# 10_SES.net
KiCad netlist of a schematic drawn in Altium Designer
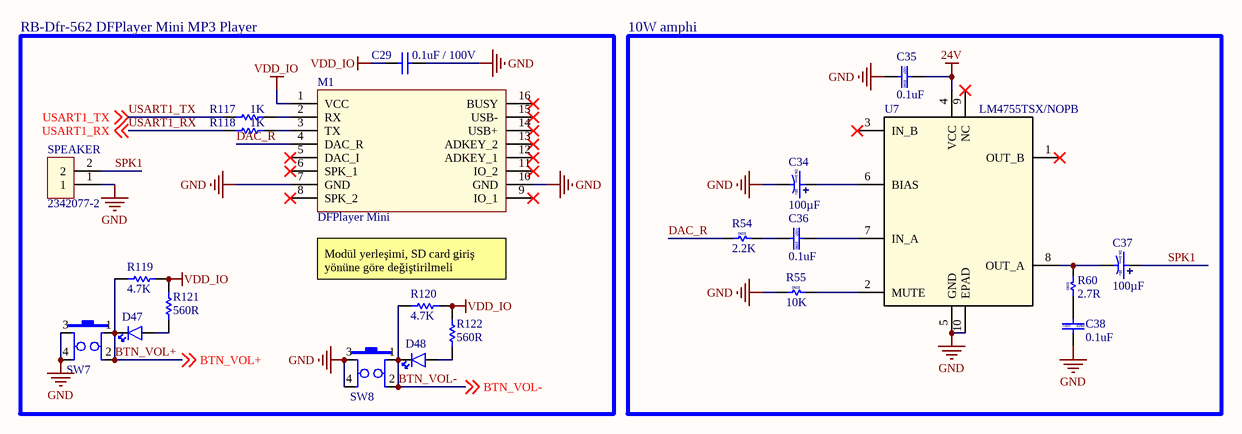
[diagram p0: 10_SES.SchDoc]

(export (version "E")
  (design (tool "Eeschema 10.0.6"))
  (components
    (comp (ref "C29")
      (value "0.1uF / 100V")
      (footprint "603C")
      (description "0.1 µF ±10% 100V Ceramic Capacitor X7R 0603 (1608 Metric)")
      (fields
        (field (name "DIGI-KEY PART NUMBER") "2679-C0603X7R101-104KNPTR-ND")
        (field (name "MANUFACTURER") "Venkel")
      )
      (libsource (lib "FKDZ_Altium_Lib") (part "CAP CER 0.1UF 100V X7R 0603"))
    )
    (comp (ref "C34")
      (value "100µF")
      (footprint "CAPALP_6.6x6.6mm")
      (description "100µF 35V Aluminum Electrolytic Capacitors Radial, Can - SMD 1000 Hrs @ 105°C")
      (fields (field (name "DIGI-KEY PART NUMBER") "493-2203-2-ND") (field (name "TOLERANCE") "±20%"))
      (libsource (lib "FKDZ_Altium_Lib") (part "CAP_ALP_100uF_35V_%20_DIA6.3mm"))
    )
    (comp (ref "C35")
      (value "0.1uF")
      (footprint "603C")
      (description "0.1 µF ±10% 100V Ceramic Capacitor X7R 0603 (1608 Metric)")
      (fields
        (field (name "DIGI-KEY PART NUMBER") "2679-C0603X7R101-104KNPTR-ND")
        (field (name "MANUFACTURER") "Venkel")
      )
      (libsource (lib "FKDZ_Altium_Lib") (part "CAP CER 0.1UF 100V X7R 0603"))
    )
    (comp (ref "C36")
      (value "0.1uF")
      (footprint "603C")
      (description "0.1 µF ±10% 100V Ceramic Capacitor X7R 0603 (1608 Metric)")
      (fields
        (field (name "DIGI-KEY PART NUMBER") "2679-C0603X7R101-104KNPTR-ND")
        (field (name "MANUFACTURER") "Venkel")
      )
      (libsource (lib "FKDZ_Altium_Lib") (part "CAP CER 0.1UF 100V X7R 0603"))
    )
    (comp (ref "C37")
      (value "100µF")
      (footprint "CAPALP_6.6x6.6mm")
      (description "100µF 35V Aluminum Electrolytic Capacitors Radial, Can - SMD 1000 Hrs @ 105°C")
      (fields (field (name "DIGI-KEY PART NUMBER") "493-2203-2-ND") (field (name "TOLERANCE") "±20%"))
      (libsource (lib "FKDZ_Altium_Lib") (part "CAP_ALP_100uF_35V_%20_DIA6.3mm"))
    )
    (comp (ref "C38")
      (value "0.1uF")
      (footprint "603C")
      (description "0.1 µF ±10% 100V Ceramic Capacitor X7R 0603 (1608 Metric)")
      (fields
        (field (name "DIGI-KEY PART NUMBER") "2679-C0603X7R101-104KNPTR-ND")
        (field (name "MANUFACTURER") "Venkel")
      )
      (libsource (lib "FKDZ_Altium_Lib") (part "CAP CER 0.1UF 100V X7R 0603"))
    )
    (comp (ref "D47")
      (value "led_green")
      (footprint "805LED")
      (description "LED 2X1.2MM 570NM GN WTR CLR SMD")
      (fields (field (name "DIGI-KEY PART NUMBER") "754-1127-1-ND"))
      (libsource (lib "FKDZ_Altium_Lib") (part "LED_GREEN_0805"))
    )
    (comp (ref "D48")
      (value "led_green")
      (footprint "805LED")
      (description "LED 2X1.2MM 570NM GN WTR CLR SMD")
      (fields (field (name "DIGI-KEY PART NUMBER") "754-1127-1-ND"))
      (libsource (lib "FKDZ_Altium_Lib") (part "LED_GREEN_0805"))
    )
    (comp (ref "M1")
      (value "DFPlayer Mini")
      (footprint "DFPLAYER MINI")
      (libsource (lib "FKDZ_Altium_Lib") (part "MP3 PLAYER MODULE DFPlayer Mini"))
    )
    (comp (ref "R54")
      (value "2.2K")
      (footprint "603R")
      (description "2.2 kOhms ±5% 0.1W, 1/10W Chip Resistor 0603 (1608 Metric) Automotive AEC-Q200 Thick Film")
      (fields (field (name "DIGI-KEY PART NUMBER") "RMCF0603JT2K20TR-ND") (field (name "TOLERANCE") "±5%"))
      (libsource (lib "FKDZ_Altium_Lib") (part "RES 2.2K OHM 5% 1/10W 0603"))
    )
    (comp (ref "R55")
      (value "10K")
      (footprint "603R")
      (description "10 kOhms ±5% 0.1W, 1/10W Chip Resistor 0603 (1608 Metric) Moisture Resistant Thick Film")
      (fields (field (name "DIGI-KEY PART NUMBER") "311-10KGRTR-ND") (field (name "MANUFACTURER") "Yageo"))
      (libsource (lib "FKDZ_Altium_Lib") (part "RES_10K_OHM_%5_0.1W_0603"))
    )
    (comp (ref "R60")
      (value "2.7R")
      (footprint "603R")
      (description "2.7 Ohms ±1% 0.1W, 1/10W Chip Resistor 0603 (1608 Metric) Automotive AEC-Q200 Thick Film")
      (fields
        (field (name "DIGI-KEY PART NUMBER") "RMCF0603FT2R70CT-ND")
        (field (name "MANUFACTURER") "Stackpole Electronics Inc")
      )
      (libsource (lib "FKDZ_Altium_Lib") (part "RES 2.7 OHM 1% 1/10W 0603"))
    )
    (comp (ref "R117")
      (value "1K")
      (footprint "603R")
      (description "1 kOhms ±5% 0.1W, 1/10W Chip Resistor 0603 (1608 Metric) Moisture Resistant Thick Film")
      (fields (field (name "DIGI-KEY PART NUMBER") "311-1.0KGRTR-ND") (field (name "MANUFACTURER") "Yageo"))
      (libsource (lib "FKDZ_Altium_Lib") (part "RES_1K_OHM_%5_0.1W_0603"))
    )
    (comp (ref "R118")
      (value "1K")
      (footprint "603R")
      (description "1 kOhms ±5% 0.1W, 1/10W Chip Resistor 0603 (1608 Metric) Moisture Resistant Thick Film")
      (fields (field (name "DIGI-KEY PART NUMBER") "311-1.0KGRTR-ND") (field (name "MANUFACTURER") "Yageo"))
      (libsource (lib "FKDZ_Altium_Lib") (part "RES_1K_OHM_%5_0.1W_0603"))
    )
    (comp (ref "R119")
      (value "4.7K")
      (footprint "603R")
      (description "4.7 kOhms ±5% 0.1W, 1/10W Chip Resistor 0603 (1608 Metric) Moisture Resistant Thick Film")
      (fields (field (name "DIGI-KEY PART NUMBER") "311-4.7KGRTR-ND") (field (name "MANUFACTURER") "Yageo"))
      (libsource (lib "FKDZ_Altium_Lib") (part "RES_4.7K_OHM_%5_0.1W_0603"))
    )
    (comp (ref "R120")
      (value "4.7K")
      (footprint "603R")
      (description "4.7 kOhms ±5% 0.1W, 1/10W Chip Resistor 0603 (1608 Metric) Moisture Resistant Thick Film")
      (fields (field (name "DIGI-KEY PART NUMBER") "311-4.7KGRTR-ND") (field (name "MANUFACTURER") "Yageo"))
      (libsource (lib "FKDZ_Altium_Lib") (part "RES_4.7K_OHM_%5_0.1W_0603"))
    )
    (comp (ref "R121")
      (value "560R")
      (footprint "603R")
      (description "560 Ohms ±5% 0.1W, 1/10W Chip Resistor 0603 (1608 Metric) Moisture Resistant Thick Film")
      (fields (field (name "DIGI-KEY PART NUMBER") "311-560GRCT-ND") (field (name "MANUFACTURER") "Yageo"))
      (libsource (lib "FKDZ_Altium_Lib") (part "RES_560_OHM_%5_0.1W_0603"))
    )
    (comp (ref "R122")
      (value "560R")
      (footprint "603R")
      (description "560 Ohms ±5% 0.1W, 1/10W Chip Resistor 0603 (1608 Metric) Moisture Resistant Thick Film")
      (fields (field (name "DIGI-KEY PART NUMBER") "311-560GRCT-ND") (field (name "MANUFACTURER") "Yageo"))
      (libsource (lib "FKDZ_Altium_Lib") (part "RES_560_OHM_%5_0.1W_0603"))
    )
    (comp (ref "SPEAKER")
      (value "2342077-2")
      (footprint "TERM BLOCK HDR 2POS 90DEG PITCH 3.81MM")
      (fields
        (field (name "DIGI-KEY PART NUMBER") "A145321-ND")
        (field (name "MANUFACTURER") "TE Connectivity AMP Connectors")
      )
      (libsource (lib "FKDZ_Altium_Lib") (part "TERM BLOCK HDR 2POS 90DEG 3.81MM"))
    )
    (comp (ref "SW7")
      (value "switch tactile")
      (footprint "SW_TACTILE_6X6mm SMT")
      (description "Tactile Switch SPST-NO Top Actuated Surface Mount")
      (fields (field (name "DIGI-KEY PART NUMBER") "CKN9112TR-ND"))
      (libsource (lib "FKDZ_Altium_Lib") (part "SW_TACTILE_6x6x4.3mm SMT"))
    )
    (comp (ref "SW8")
      (value "switch tactile")
      (footprint "SW_TACTILE_6X6mm SMT")
      (description "Tactile Switch SPST-NO Top Actuated Surface Mount")
      (fields (field (name "DIGI-KEY PART NUMBER") "CKN9112TR-ND"))
      (libsource (lib "FKDZ_Altium_Lib") (part "SW_TACTILE_6x6x4.3mm SMT"))
    )
    (comp (ref "U7")
      (value "LM4755TSX/NOPB")
      (footprint "TO-263-10 (9 Leads + Tab)")
      (description "Amplifier IC 2-Channel (Stereo) Class AB DDPAK/TO-263-9")
      (fields
        (field (name "MANUFACTURER") "Texas Instruments")
        (field (name "DIGIKEY PART NUMBER") "296-46304-1-ND")
      )
      (libsource (lib "FKDZ_Altium_Lib") (part "IC AMP CLASS AB STER 11W TO263-9 LM4755TSXNOPB"))
    )
  )
  (nets
    (net (code "1") (name "/DAC_R") (class "Default")
      (node (ref "M1") (pin "4") (pinfunction "DAC_R_4") (pintype "passive"))
      (node (ref "R54") (pin "1") (pinfunction "1_1") (pintype "passive"))
    )
    (net (code "2") (name "/SPK1") (class "Default")
      (node (ref "C37") (pin "1") (pinfunction "1_1") (pintype "passive"))
      (node (ref "SPEAKER") (pin "2") (pinfunction "2_2") (pintype "passive"))
    )
    (net (code "3") (name "24V") (class "Default")
      (node (ref "C35") (pin "2") (pinfunction "2_2") (pintype "passive"))
      (node (ref "U7") (pin "4") (pinfunction "VCC_4") (pintype "power_in"))
    )
    (net (code "4") (name "BTN_VOL+") (class "Default")
      (node (ref "D47") (pin "2") (pinfunction "K_2") (pintype "passive"))
      (node (ref "R119") (pin "1") (pinfunction "1_1") (pintype "passive"))
      (node (ref "SW7") (pin "1") (pinfunction "1_1") (pintype "passive"))
      (node (ref "SW7") (pin "2") (pinfunction "2_2") (pintype "passive"))
    )
    (net (code "5") (name "BTN_VOL-") (class "Default")
      (node (ref "D48") (pin "2") (pinfunction "K_2") (pintype "passive"))
      (node (ref "R120") (pin "1") (pinfunction "1_1") (pintype "passive"))
      (node (ref "SW8") (pin "1") (pinfunction "1_1") (pintype "passive"))
      (node (ref "SW8") (pin "2") (pinfunction "2_2") (pintype "passive"))
    )
    (net (code "6") (name "GND") (class "Default")
      (node (ref "C29") (pin "2") (pinfunction "2_2") (pintype "passive"))
      (node (ref "C34") (pin "2") (pinfunction "2_2") (pintype "passive"))
      (node (ref "C35") (pin "1") (pinfunction "1_1") (pintype "passive"))
      (node (ref "C38") (pin "1") (pinfunction "1_1") (pintype "passive"))
      (node (ref "M1") (pin "10") (pinfunction "GND_10") (pintype "passive"))
      (node (ref "M1") (pin "7") (pinfunction "GND_7") (pintype "passive"))
      (node (ref "R55") (pin "1") (pinfunction "1_1") (pintype "passive"))
      (node (ref "SPEAKER") (pin "1") (pinfunction "1_1") (pintype "passive"))
      (node (ref "SW7") (pin "3") (pinfunction "3_3") (pintype "passive"))
      (node (ref "SW7") (pin "4") (pinfunction "4_4") (pintype "passive"))
      (node (ref "SW8") (pin "3") (pinfunction "3_3") (pintype "passive"))
      (node (ref "SW8") (pin "4") (pinfunction "4_4") (pintype "passive"))
      (node (ref "U7") (pin "10") (pinfunction "EPAD_10") (pintype "power_in"))
      (node (ref "U7") (pin "5") (pinfunction "GND_5") (pintype "power_in"))
    )
    (net (code "7") (name "Net-(C36-Pad1)") (class "Default")
      (node (ref "C36") (pin "1") (pinfunction "1_1") (pintype "passive"))
      (node (ref "R54") (pin "2") (pinfunction "2_2") (pintype "passive"))
    )
    (net (code "8") (name "Net-(C38-Pad2)") (class "Default")
      (node (ref "C38") (pin "2") (pinfunction "2_2") (pintype "passive"))
      (node (ref "R60") (pin "1") (pinfunction "1_1") (pintype "passive"))
    )
    (net (code "9") (name "Net-(D47-A)") (class "Default")
      (node (ref "D47") (pin "1") (pinfunction "A_1") (pintype "passive"))
      (node (ref "R121") (pin "1") (pinfunction "1_1") (pintype "passive"))
    )
    (net (code "10") (name "Net-(D48-A)") (class "Default")
      (node (ref "D48") (pin "1") (pinfunction "A_1") (pintype "passive"))
      (node (ref "R122") (pin "1") (pinfunction "1_1") (pintype "passive"))
    )
    (net (code "11") (name "Net-(M1-RX)") (class "Default")
      (node (ref "M1") (pin "2") (pinfunction "RX_2") (pintype "passive"))
      (node (ref "R117") (pin "2") (pinfunction "2_2") (pintype "passive"))
    )
    (net (code "12") (name "Net-(M1-TX)") (class "Default")
      (node (ref "M1") (pin "3") (pinfunction "TX_3") (pintype "passive"))
      (node (ref "R118") (pin "2") (pinfunction "2_2") (pintype "passive"))
    )
    (net (code "13") (name "Net-(U7-BIAS)") (class "Default")
      (node (ref "C34") (pin "1") (pinfunction "1_1") (pintype "passive"))
      (node (ref "U7") (pin "6") (pinfunction "BIAS_6") (pintype "passive"))
    )
    (net (code "14") (name "Net-(U7-IN_A)") (class "Default")
      (node (ref "C36") (pin "2") (pinfunction "2_2") (pintype "passive"))
      (node (ref "U7") (pin "7") (pinfunction "IN_A_7") (pintype "passive"))
    )
    (net (code "15") (name "Net-(U7-MUTE)") (class "Default")
      (node (ref "R55") (pin "2") (pinfunction "2_2") (pintype "passive"))
      (node (ref "U7") (pin "2") (pinfunction "MUTE_2") (pintype "passive"))
    )
    (net (code "16") (name "Net-(U7-OUT_A)") (class "Default")
      (node (ref "C37") (pin "2") (pinfunction "2_2") (pintype "passive"))
      (node (ref "R60") (pin "2") (pinfunction "2_2") (pintype "passive"))
      (node (ref "U7") (pin "8") (pinfunction "OUT_A_8") (pintype "passive"))
    )
    (net (code "17") (name "USART1_RX") (class "Default")
      (node (ref "R118") (pin "1") (pinfunction "1_1") (pintype "passive"))
    )
    (net (code "18") (name "USART1_TX") (class "Default")
      (node (ref "R117") (pin "1") (pinfunction "1_1") (pintype "passive"))
    )
    (net (code "19") (name "VDD_IO") (class "Default")
      (node (ref "C29") (pin "1") (pinfunction "1_1") (pintype "passive"))
      (node (ref "M1") (pin "1") (pinfunction "VCC_1") (pintype "passive"))
      (node (ref "R119") (pin "2") (pinfunction "2_2") (pintype "passive"))
      (node (ref "R120") (pin "2") (pinfunction "2_2") (pintype "passive"))
      (node (ref "R121") (pin "2") (pinfunction "2_2") (pintype "passive"))
      (node (ref "R122") (pin "2") (pinfunction "2_2") (pintype "passive"))
    )
    (net (code "20") (name "unconnected-(M1-ADKEY_1-Pad12)") (class "Default")
      (node (ref "M1") (pin "12") (pinfunction "ADKEY_1_12") (pintype "passive+no_connect"))
    )
    (net (code "21") (name "unconnected-(M1-ADKEY_2-Pad13)") (class "Default")
      (node (ref "M1") (pin "13") (pinfunction "ADKEY_2_13") (pintype "passive+no_connect"))
    )
    (net (code "22") (name "unconnected-(M1-BUSY-Pad16)") (class "Default")
      (node (ref "M1") (pin "16") (pinfunction "BUSY_16") (pintype "passive+no_connect"))
    )
    (net (code "23") (name "unconnected-(M1-DAC_I-Pad5)") (class "Default")
      (node (ref "M1") (pin "5") (pinfunction "DAC_I_5") (pintype "passive+no_connect"))
    )
    (net (code "24") (name "unconnected-(M1-IO_1-Pad9)") (class "Default")
      (node (ref "M1") (pin "9") (pinfunction "IO_1_9") (pintype "passive+no_connect"))
    )
    (net (code "25") (name "unconnected-(M1-IO_2-Pad11)") (class "Default")
      (node (ref "M1") (pin "11") (pinfunction "IO_2_11") (pintype "passive+no_connect"))
    )
    (net (code "26") (name "unconnected-(M1-SPK_1-Pad6)") (class "Default")
      (node (ref "M1") (pin "6") (pinfunction "SPK_1_6") (pintype "passive+no_connect"))
    )
    (net (code "27") (name "unconnected-(M1-SPK_2-Pad8)") (class "Default")
      (node (ref "M1") (pin "8") (pinfunction "SPK_2_8") (pintype "passive+no_connect"))
    )
    (net (code "28") (name "unconnected-(M1-USB+-Pad14)") (class "Default")
      (node (ref "M1") (pin "14") (pinfunction "USB+_14") (pintype "passive+no_connect"))
    )
    (net (code "29") (name "unconnected-(M1-USB--Pad15)") (class "Default")
      (node (ref "M1") (pin "15") (pinfunction "USB-_15") (pintype "passive+no_connect"))
    )
    (net (code "30") (name "unconnected-(U7-IN_B-Pad3)") (class "Default")
      (node (ref "U7") (pin "3") (pinfunction "IN_B_3") (pintype "passive+no_connect"))
    )
    (net (code "31") (name "unconnected-(U7-NC-Pad9)") (class "Default")
      (node (ref "U7") (pin "9") (pinfunction "NC_9") (pintype "passive+no_connect"))
    )
    (net (code "32") (name "unconnected-(U7-OUT_B-Pad1)") (class "Default")
      (node (ref "U7") (pin "1") (pinfunction "OUT_B_1") (pintype "passive+no_connect"))
    )
  )
)
